# 10_USB.net
KiCad netlist of a schematic drawn in Altium Designer
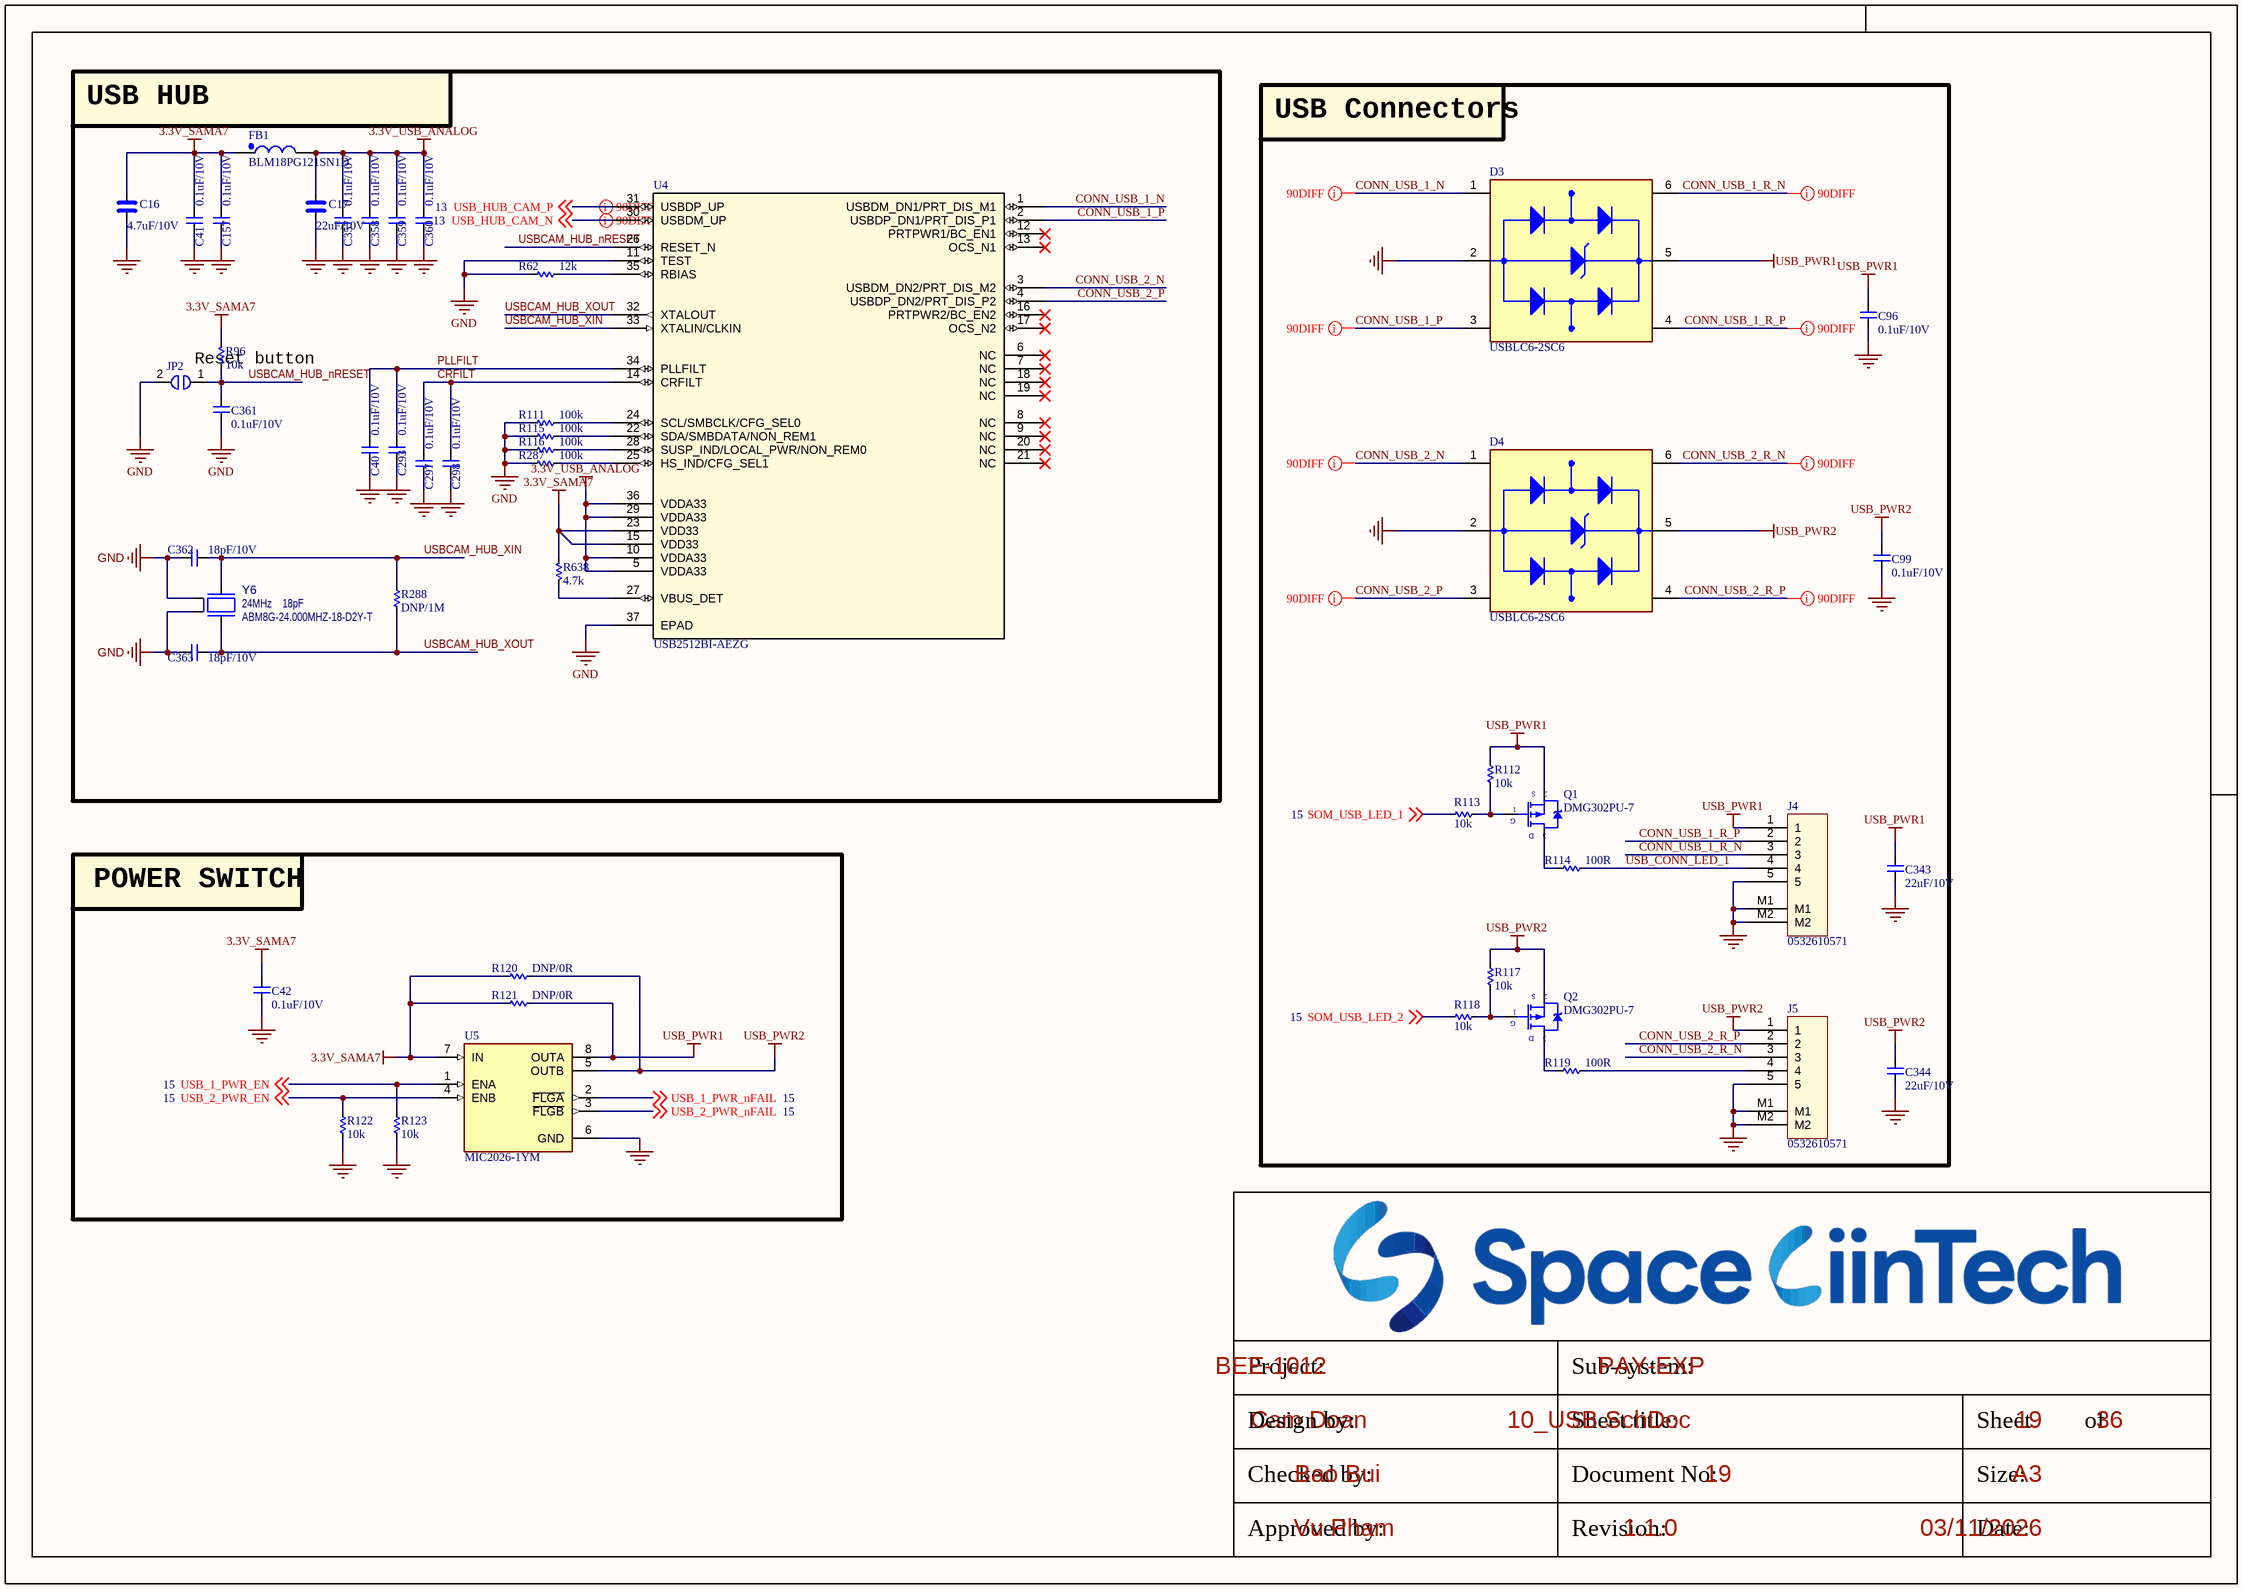
[diagram p0: 10_USB.SchDoc]

(export (version "E")
  (design (tool "Eeschema 10.0.6"))
  (components
    (comp (ref "C16")
      (value "4.7uF/10V")
      (footprint "CAP_C_1608X80")
      (description "CAP CHIP High Value")
      (libsource (lib "LABLIB") (part "_CAP_C_High_2"))
    )
    (comp (ref "C17")
      (value "22uF/10V")
      (footprint "CAP_C_1608X80")
      (description "CAP CHIP High Value")
      (libsource (lib "LABLIB") (part "_CAP_C_High_2"))
    )
    (comp (ref "C40")
      (value "0.1uF/10V")
      (footprint "CAP_C_1005X60")
      (description "CAP CHIP")
      (libsource (lib "LABLIB") (part "_CAP_C_2"))
    )
    (comp (ref "C41")
      (value "0.1uF/10V")
      (footprint "CAP_C_1005X60")
      (description "CAP CHIP")
      (libsource (lib "LABLIB") (part "_CAP_C_2"))
    )
    (comp (ref "C42")
      (value "0.1uF/10V")
      (footprint "CAP_C_1005X60")
      (description "CAP")
      (libsource (lib "LABLIB") (part "_CAP_C_2"))
    )
    (comp (ref "C96")
      (value "0.1uF/10V")
      (footprint "CAP_C_1005X60")
      (description "CAP")
      (libsource (lib "LABLIB") (part "_CAP_C_2"))
    )
    (comp (ref "C99")
      (value "0.1uF/10V")
      (footprint "CAP_C_1005X60")
      (description "CAP")
      (libsource (lib "LABLIB") (part "_CAP_C_2"))
    )
    (comp (ref "C157")
      (value "0.1uF/10V")
      (footprint "CAP_C_1005X60")
      (description "CAP CHIP")
      (libsource (lib "LABLIB") (part "_CAP_C_2"))
    )
    (comp (ref "C293")
      (value "0.1uF/10V")
      (footprint "CAP_C_1005X60")
      (description "CAP CHIP")
      (libsource (lib "LABLIB") (part "_CAP_C_2"))
    )
    (comp (ref "C297")
      (value "0.1uF/10V")
      (footprint "CAP_C_1005X60")
      (description "CAP CHIP")
      (libsource (lib "LABLIB") (part "_CAP_C_2"))
    )
    (comp (ref "C298")
      (value "0.1uF/10V")
      (footprint "CAP_C_1005X60")
      (description "CAP CHIP")
      (libsource (lib "LABLIB") (part "_CAP_C_2"))
    )
    (comp (ref "C343")
      (value "22uF/10V")
      (footprint "CAP_C_1608X80")
      (description "CAP")
      (libsource (lib "LABLIB") (part "_CAP_C_2"))
    )
    (comp (ref "C344")
      (value "22uF/10V")
      (footprint "CAP_C_1608X80")
      (description "CAP")
      (libsource (lib "LABLIB") (part "_CAP_C_2"))
    )
    (comp (ref "C357")
      (value "0.1uF/10V")
      (footprint "CAP_C_1005X60")
      (description "CAP CHIP")
      (libsource (lib "LABLIB") (part "_CAP_C_2"))
    )
    (comp (ref "C358")
      (value "0.1uF/10V")
      (footprint "CAP_C_1005X60")
      (description "CAP CHIP")
      (libsource (lib "LABLIB") (part "_CAP_C_2"))
    )
    (comp (ref "C359")
      (value "0.1uF/10V")
      (footprint "CAP_C_1005X60")
      (description "CAP CHIP")
      (libsource (lib "LABLIB") (part "_CAP_C_2"))
    )
    (comp (ref "C360")
      (value "0.1uF/10V")
      (footprint "CAP_C_1005X60")
      (description "CAP CHIP")
      (libsource (lib "LABLIB") (part "_CAP_C_2"))
    )
    (comp (ref "C361")
      (value "0.1uF/10V")
      (footprint "CAP_C_1005X60")
      (description "CAP CHIP")
      (libsource (lib "LABLIB") (part "_CAP_C_2"))
    )
    (comp (ref "C362")
      (value "18pF/10V")
      (footprint "CAP_C_1005X60")
      (description "CAP CHIP")
      (libsource (lib "LABLIB") (part "_CAP_C_2"))
    )
    (comp (ref "C363")
      (value "18pF/10V")
      (footprint "CAP_C_1005X60")
      (description "CAP CHIP")
      (libsource (lib "LABLIB") (part "_CAP_C_2"))
    )
    (comp (ref "D3")
      (value "USBLC6-2SC6")
      (footprint "SOT95P280X145-6N")
      (description "17V Clamp 5A (8/20Âµs) Ipp Tvs Diode Surface Mount SOT-23-6")
      (fields (field (name "MF") "STMicroelectronics"))
      (libsource (lib "USBLC6-2SC6") (part "USBLC6-2SC6"))
    )
    (comp (ref "D4")
      (value "USBLC6-2SC6")
      (footprint "SOT95P280X145-6N")
      (description "17V Clamp 5A (8/20Âµs) Ipp Tvs Diode Surface Mount SOT-23-6")
      (fields (field (name "MF") "STMicroelectronics"))
      (libsource (lib "USBLC6-2SC6") (part "USBLC6-2SC6"))
    )
    (comp (ref "FB1")
      (value "BLM18PG121SN1D")
      (footprint "IND_C_1608X60")
      (libsource (lib "LABLIB") (part "_IND"))
    )
    (comp (ref "J4")
      (value "0532610571")
      (footprint "MOLEX_0532610571")
      (libsource (lib "LABLIB") (part "Header 5x1_2M"))
    )
    (comp (ref "J5")
      (value "0532610571")
      (footprint "MOLEX_0532610571")
      (libsource (lib "LABLIB") (part "Header 5x1_2M"))
    )
    (comp (ref "JP2")
      (value "~")
      (footprint "TESTPOINT_SHORT_120X100_60")
      (libsource (lib "LABLIB") (part "JUMPER_1_1"))
    )
    (comp (ref "Q1")
      (value "DMG302PU-7")
      (footprint "SOT95P240X120-3N")
      (libsource (lib "LABLIB") (part "MOSFET_P_GSD"))
    )
    (comp (ref "Q2")
      (value "DMG302PU-7")
      (footprint "SOT95P240X120-3N")
      (libsource (lib "LABLIB") (part "MOSFET_P_GSD"))
    )
    (comp (ref "R62")
      (value "12k")
      (footprint "RES_C_1005X40")
      (description "RES")
      (libsource (lib "LABLIB") (part "_RES_B_2"))
    )
    (comp (ref "R96")
      (value "10k")
      (footprint "RES_C_1005X40")
      (description "RES")
      (libsource (lib "LABLIB") (part "_RES_B_2"))
    )
    (comp (ref "R111")
      (value "100k")
      (footprint "RES_C_1005X40")
      (description "RES")
      (libsource (lib "LABLIB") (part "_RES_B_2"))
    )
    (comp (ref "R112")
      (value "10k")
      (footprint "RES_C_1005X40")
      (description "RES")
      (libsource (lib "LABLIB") (part "_RES_B_2"))
    )
    (comp (ref "R113")
      (value "10k")
      (footprint "RES_C_1005X40")
      (description "RES")
      (libsource (lib "LABLIB") (part "_RES_B_2"))
    )
    (comp (ref "R114")
      (value "100R")
      (footprint "RES_C_1005X40")
      (description "RES")
      (libsource (lib "LABLIB") (part "_RES_B_2"))
    )
    (comp (ref "R115")
      (value "100k")
      (footprint "RES_C_1005X40")
      (description "RES")
      (libsource (lib "LABLIB") (part "_RES_B_2"))
    )
    (comp (ref "R116")
      (value "100k")
      (footprint "RES_C_1005X40")
      (description "RES")
      (libsource (lib "LABLIB") (part "_RES_B_2"))
    )
    (comp (ref "R117")
      (value "10k")
      (footprint "RES_C_1005X40")
      (description "RES")
      (libsource (lib "LABLIB") (part "_RES_B_2"))
    )
    (comp (ref "R118")
      (value "10k")
      (footprint "RES_C_1005X40")
      (description "RES")
      (libsource (lib "LABLIB") (part "_RES_B_2"))
    )
    (comp (ref "R119")
      (value "100R")
      (footprint "RES_C_1005X40")
      (description "RES")
      (libsource (lib "LABLIB") (part "_RES_B_2"))
    )
    (comp (ref "R120")
      (value "DNP/0R")
      (footprint "RES_C_1005X40")
      (description "RES")
      (libsource (lib "LABLIB") (part "_RES_B_2"))
    )
    (comp (ref "R121")
      (value "DNP/0R")
      (footprint "RES_C_1005X40")
      (description "RES")
      (libsource (lib "LABLIB") (part "_RES_B_2"))
    )
    (comp (ref "R122")
      (value "10k")
      (footprint "RES_C_1005X40")
      (description "RES")
      (libsource (lib "LABLIB") (part "_RES_B_2"))
    )
    (comp (ref "R123")
      (value "10k")
      (footprint "RES_C_1005X40")
      (description "RES")
      (libsource (lib "LABLIB") (part "_RES_B_2"))
    )
    (comp (ref "R287")
      (value "100k")
      (footprint "RES_C_1005X40")
      (description "RES")
      (libsource (lib "LABLIB") (part "_RES_B_2"))
    )
    (comp (ref "R288")
      (value "DNP/1M")
      (footprint "RES_C_1005X40")
      (description "RES")
      (libsource (lib "LABLIB") (part "_RES_B_2"))
    )
    (comp (ref "R638")
      (value "4.7k")
      (footprint "RES_C_1005X40")
      (description "RES")
      (libsource (lib "LABLIB") (part "_RES_B_2"))
    )
    (comp (ref "U4")
      (value "USB2512BI-AEZG")
      (footprint "QFN36_6X6MC_MCH")
      (description "Description")
      (fields (field (name "COPYRIGHT") "Copyright (C) 2026 Ultra Librarian. All rights reserved."))
      (libsource (lib "LABLIB") (part "IC_USB_HUB_USB2512BI-AEZG"))
    )
    (comp (ref "U5")
      (value "MIC2026-1YM")
      (footprint "SOIC127P602X173-8N")
      (description "Power Switch/Driver 1:2 N-Channel 1.25A 8-SOIC")
      (fields (field (name "MF") "Microchip"))
      (libsource (lib "LABLIB") (part "IC_PWRSW_MIC2026-1YM"))
    )
    (comp (ref "Y6")
      (value "24MHz")
      (footprint "CRYSTAL_ABM8G")
      (description "Crystal")
      (fields
        (field (name "LOAD CAPACITANCE") "18pF")
        (field (name "MANUFACTURER PART NUMBER 1") "ABM8G-24.000MHZ-18-D2Y-T")
        (field (name "Comment") "Crystal 4 Pins")
        (field (name "OWNER") "Mark Loper")
      )
      (libsource (lib "MCHP-CDB") (part "Crystal 4 Pins"))
    )
  )
  (nets
    (net (code "1") (name "/CONN_USB_1_N") (class "Default")
      (node (ref "D3") (pin "1") (pinfunction "I/O1_IN_1") (pintype "passive"))
      (node (ref "U4") (pin "1") (pinfunction "USBDM_DN1/PRT_DIS_M1_1") (pintype "bidirectional"))
    )
    (net (code "2") (name "/CONN_USB_1_P") (class "Default")
      (node (ref "D3") (pin "3") (pinfunction "I/O2_IN_3") (pintype "passive"))
      (node (ref "U4") (pin "2") (pinfunction "USBDP_DN1/PRT_DIS_P1_2") (pintype "bidirectional"))
    )
    (net (code "3") (name "/CONN_USB_1_R_N") (class "Default")
      (node (ref "D3") (pin "6") (pinfunction "I/O1_OUT_6") (pintype "passive"))
      (node (ref "J4") (pin "3") (pinfunction "3_3") (pintype "passive"))
    )
    (net (code "4") (name "/CONN_USB_1_R_P") (class "Default")
      (node (ref "D3") (pin "4") (pinfunction "I/O2_OUT_4") (pintype "passive"))
      (node (ref "J4") (pin "2") (pinfunction "2_2") (pintype "passive"))
    )
    (net (code "5") (name "/CONN_USB_2_N") (class "Default")
      (node (ref "D4") (pin "1") (pinfunction "I/O1_IN_1") (pintype "passive"))
      (node (ref "U4") (pin "3") (pinfunction "USBDM_DN2/PRT_DIS_M2_3") (pintype "bidirectional"))
    )
    (net (code "6") (name "/CONN_USB_2_P") (class "Default")
      (node (ref "D4") (pin "3") (pinfunction "I/O2_IN_3") (pintype "passive"))
      (node (ref "U4") (pin "4") (pinfunction "USBDP_DN2/PRT_DIS_P2_4") (pintype "bidirectional"))
    )
    (net (code "7") (name "/CONN_USB_2_R_N") (class "Default")
      (node (ref "D4") (pin "6") (pinfunction "I/O1_OUT_6") (pintype "passive"))
      (node (ref "J5") (pin "3") (pinfunction "3_3") (pintype "passive"))
    )
    (net (code "8") (name "/CONN_USB_2_R_P") (class "Default")
      (node (ref "D4") (pin "4") (pinfunction "I/O2_OUT_4") (pintype "passive"))
      (node (ref "J5") (pin "2") (pinfunction "2_2") (pintype "passive"))
    )
    (net (code "9") (name "/CRFILT") (class "Default")
      (node (ref "C297") (pin "2") (pinfunction "2_2") (pintype "passive"))
      (node (ref "C298") (pin "2") (pinfunction "2_2") (pintype "passive"))
      (node (ref "U4") (pin "14") (pinfunction "CRFILT_14") (pintype "bidirectional"))
    )
    (net (code "10") (name "/PLLFILT") (class "Default")
      (node (ref "C293") (pin "2") (pinfunction "2_2") (pintype "passive"))
      (node (ref "C40") (pin "2") (pinfunction "2_2") (pintype "passive"))
      (node (ref "U4") (pin "34") (pinfunction "PLLFILT_34") (pintype "bidirectional"))
    )
    (net (code "11") (name "/USBCAM_HUB_XIN") (class "Default")
      (node (ref "C362") (pin "1") (pinfunction "1_1") (pintype "passive"))
      (node (ref "R288") (pin "1") (pinfunction "1_1") (pintype "passive"))
      (node (ref "U4") (pin "33") (pinfunction "XTALIN/CLKIN_33") (pintype "input"))
      (node (ref "Y6") (pin "3") (pinfunction "Osc2_3") (pintype "passive"))
    )
    (net (code "12") (name "/USBCAM_HUB_XOUT") (class "Default")
      (node (ref "C363") (pin "1") (pinfunction "1_1") (pintype "passive"))
      (node (ref "R288") (pin "2") (pinfunction "2_2") (pintype "passive"))
      (node (ref "U4") (pin "32") (pinfunction "XTALOUT_32") (pintype "output"))
      (node (ref "Y6") (pin "1") (pinfunction "Osc1_1") (pintype "passive"))
    )
    (net (code "13") (name "/USBCAM_HUB_nRESET") (class "Default")
      (node (ref "C361") (pin "2") (pinfunction "2_2") (pintype "passive"))
      (node (ref "JP2") (pin "1") (pinfunction "1_1") (pintype "passive"))
      (node (ref "R96") (pin "2") (pinfunction "2_2") (pintype "passive"))
      (node (ref "U4") (pin "26") (pinfunction "RESET_N_26") (pintype "bidirectional"))
    )
    (net (code "14") (name "/USB_CONN_LED_1") (class "Default")
      (node (ref "J4") (pin "4") (pinfunction "4_4") (pintype "passive"))
      (node (ref "R114") (pin "2") (pinfunction "2_2") (pintype "passive"))
    )
    (net (code "15") (name "3.3V_SAMA7") (class "Default")
      (node (ref "C157") (pin "2") (pinfunction "2_2") (pintype "passive"))
      (node (ref "C16") (pin "1") (pinfunction "1_1") (pintype "passive"))
      (node (ref "C41") (pin "2") (pinfunction "2_2") (pintype "passive"))
      (node (ref "C42") (pin "2") (pinfunction "2_2") (pintype "passive"))
      (node (ref "FB1") (pin "1") (pinfunction "1_1") (pintype "passive"))
      (node (ref "R120") (pin "2") (pinfunction "2_2") (pintype "passive"))
      (node (ref "R121") (pin "2") (pinfunction "2_2") (pintype "passive"))
      (node (ref "R638") (pin "1") (pinfunction "1_1") (pintype "passive"))
      (node (ref "R96") (pin "1") (pinfunction "1_1") (pintype "passive"))
      (node (ref "U4") (pin "15") (pinfunction "VDD33_15") (pintype "power_in"))
      (node (ref "U4") (pin "23") (pinfunction "VDD33_23") (pintype "power_in"))
      (node (ref "U5") (pin "7") (pinfunction "IN_7") (pintype "input"))
    )
    (net (code "16") (name "3.3V_USB_ANALOG") (class "Default")
      (node (ref "C17") (pin "1") (pinfunction "1_1") (pintype "passive"))
      (node (ref "C357") (pin "2") (pinfunction "2_2") (pintype "passive"))
      (node (ref "C358") (pin "2") (pinfunction "2_2") (pintype "passive"))
      (node (ref "C359") (pin "2") (pinfunction "2_2") (pintype "passive"))
      (node (ref "C360") (pin "2") (pinfunction "2_2") (pintype "passive"))
      (node (ref "FB1") (pin "2") (pinfunction "2_2") (pintype "passive"))
      (node (ref "U4") (pin "10") (pinfunction "VDDA33_10") (pintype "power_in"))
      (node (ref "U4") (pin "29") (pinfunction "VDDA33_29") (pintype "power_in"))
      (node (ref "U4") (pin "36") (pinfunction "VDDA33_36") (pintype "power_in"))
      (node (ref "U4") (pin "5") (pinfunction "VDDA33_5") (pintype "power_in"))
    )
    (net (code "17") (name "GND") (class "Default")
      (node (ref "C157") (pin "1") (pinfunction "1_1") (pintype "passive"))
      (node (ref "C16") (pin "2") (pinfunction "2_2") (pintype "passive"))
      (node (ref "C17") (pin "2") (pinfunction "2_2") (pintype "passive"))
      (node (ref "C293") (pin "1") (pinfunction "1_1") (pintype "passive"))
      (node (ref "C297") (pin "1") (pinfunction "1_1") (pintype "passive"))
      (node (ref "C298") (pin "1") (pinfunction "1_1") (pintype "passive"))
      (node (ref "C343") (pin "1") (pinfunction "1_1") (pintype "passive"))
      (node (ref "C344") (pin "1") (pinfunction "1_1") (pintype "passive"))
      (node (ref "C357") (pin "1") (pinfunction "1_1") (pintype "passive"))
      (node (ref "C358") (pin "1") (pinfunction "1_1") (pintype "passive"))
      (node (ref "C359") (pin "1") (pinfunction "1_1") (pintype "passive"))
      (node (ref "C360") (pin "1") (pinfunction "1_1") (pintype "passive"))
      (node (ref "C361") (pin "1") (pinfunction "1_1") (pintype "passive"))
      (node (ref "C362") (pin "2") (pinfunction "2_2") (pintype "passive"))
      (node (ref "C363") (pin "2") (pinfunction "2_2") (pintype "passive"))
      (node (ref "C40") (pin "1") (pinfunction "1_1") (pintype "passive"))
      (node (ref "C41") (pin "1") (pinfunction "1_1") (pintype "passive"))
      (node (ref "C42") (pin "1") (pinfunction "1_1") (pintype "passive"))
      (node (ref "C96") (pin "1") (pinfunction "1_1") (pintype "passive"))
      (node (ref "C99") (pin "1") (pinfunction "1_1") (pintype "passive"))
      (node (ref "D3") (pin "2") (pinfunction "GND_2") (pintype "power_in"))
      (node (ref "D4") (pin "2") (pinfunction "GND_2") (pintype "power_in"))
      (node (ref "J4") (pin "5") (pinfunction "5_5") (pintype "passive"))
      (node (ref "J4") (pin "M1") (pinfunction "M1_M1") (pintype "passive"))
      (node (ref "J4") (pin "M2") (pinfunction "M2_M2") (pintype "passive"))
      (node (ref "J5") (pin "5") (pinfunction "5_5") (pintype "passive"))
      (node (ref "J5") (pin "M1") (pinfunction "M1_M1") (pintype "passive"))
      (node (ref "J5") (pin "M2") (pinfunction "M2_M2") (pintype "passive"))
      (node (ref "JP2") (pin "2") (pinfunction "2_2") (pintype "passive"))
      (node (ref "R111") (pin "1") (pinfunction "1_1") (pintype "passive"))
      (node (ref "R115") (pin "1") (pinfunction "1_1") (pintype "passive"))
      (node (ref "R116") (pin "1") (pinfunction "1_1") (pintype "passive"))
      (node (ref "R122") (pin "2") (pinfunction "2_2") (pintype "passive"))
      (node (ref "R123") (pin "2") (pinfunction "2_2") (pintype "passive"))
      (node (ref "R287") (pin "1") (pinfunction "1_1") (pintype "passive"))
      (node (ref "R62") (pin "1") (pinfunction "1_1") (pintype "passive"))
      (node (ref "U4") (pin "11") (pinfunction "TEST_11") (pintype "bidirectional"))
      (node (ref "U4") (pin "37") (pinfunction "EPAD_37") (pintype "passive"))
      (node (ref "U5") (pin "6") (pinfunction "GND_6") (pintype "power_in"))
      (node (ref "Y6") (pin "2") (pinfunction "GND_2") (pintype "power_in"))
      (node (ref "Y6") (pin "4") (pinfunction "GND_4") (pintype "power_in"))
    )
    (net (code "18") (name "Net-(J5-Pad4)") (class "Default")
      (node (ref "J5") (pin "4") (pinfunction "4_4") (pintype "passive"))
      (node (ref "R119") (pin "2") (pinfunction "2_2") (pintype "passive"))
    )
    (net (code "19") (name "Net-(Q1-D)") (class "Default")
      (node (ref "Q1") (pin "3") (pinfunction "D_3") (pintype "passive"))
      (node (ref "R114") (pin "1") (pinfunction "1_1") (pintype "passive"))
    )
    (net (code "20") (name "Net-(Q1-G)") (class "Default")
      (node (ref "Q1") (pin "1") (pinfunction "G_1") (pintype "passive"))
      (node (ref "R112") (pin "2") (pinfunction "2_2") (pintype "passive"))
      (node (ref "R113") (pin "2") (pinfunction "2_2") (pintype "passive"))
    )
    (net (code "21") (name "Net-(Q2-D)") (class "Default")
      (node (ref "Q2") (pin "3") (pinfunction "D_3") (pintype "passive"))
      (node (ref "R119") (pin "1") (pinfunction "1_1") (pintype "passive"))
    )
    (net (code "22") (name "Net-(Q2-G)") (class "Default")
      (node (ref "Q2") (pin "1") (pinfunction "G_1") (pintype "passive"))
      (node (ref "R117") (pin "2") (pinfunction "2_2") (pintype "passive"))
      (node (ref "R118") (pin "2") (pinfunction "2_2") (pintype "passive"))
    )
    (net (code "23") (name "Net-(U4-HS_IND{slash}CFG_SEL1)") (class "Default")
      (node (ref "R287") (pin "2") (pinfunction "2_2") (pintype "passive"))
      (node (ref "U4") (pin "25") (pinfunction "HS_IND/CFG_SEL1_25") (pintype "bidirectional"))
    )
    (net (code "24") (name "Net-(U4-RBIAS)") (class "Default")
      (node (ref "R62") (pin "2") (pinfunction "2_2") (pintype "passive"))
      (node (ref "U4") (pin "35") (pinfunction "RBIAS_35") (pintype "bidirectional"))
    )
    (net (code "25") (name "Net-(U4-SCL{slash}SMBCLK{slash}CFG_SEL0)") (class "Default")
      (node (ref "R111") (pin "2") (pinfunction "2_2") (pintype "passive"))
      (node (ref "U4") (pin "24") (pinfunction "SCL/SMBCLK/CFG_SEL0_24") (pintype "bidirectional"))
    )
    (net (code "26") (name "Net-(U4-SDA{slash}SMBDATA{slash}NON_REM1)") (class "Default")
      (node (ref "R115") (pin "2") (pinfunction "2_2") (pintype "passive"))
      (node (ref "U4") (pin "22") (pinfunction "SDA/SMBDATA/NON_REM1_22") (pintype "bidirectional"))
    )
    (net (code "27") (name "Net-(U4-SUSP_IND{slash}LOCAL_PWR{slash}NON_REM0)") (class "Default")
      (node (ref "R116") (pin "2") (pinfunction "2_2") (pintype "passive"))
      (node (ref "U4") (pin "28") (pinfunction "SUSP_IND/LOCAL_PWR/NON_REM0_28") (pintype "bidirectional"))
    )
    (net (code "28") (name "Net-(U4-VBUS_DET)") (class "Default")
      (node (ref "R638") (pin "2") (pinfunction "2_2") (pintype "passive"))
      (node (ref "U4") (pin "27") (pinfunction "VBUS_DET_27") (pintype "bidirectional"))
    )
    (net (code "29") (name "SOM_USB_LED_1") (class "Default")
      (node (ref "R113") (pin "1") (pinfunction "1_1") (pintype "passive"))
    )
    (net (code "30") (name "SOM_USB_LED_2") (class "Default")
      (node (ref "R118") (pin "1") (pinfunction "1_1") (pintype "passive"))
    )
    (net (code "31") (name "USB_1_PWR_EN") (class "Default")
      (node (ref "R123") (pin "1") (pinfunction "1_1") (pintype "passive"))
      (node (ref "U5") (pin "1") (pinfunction "ENA_1") (pintype "input"))
    )
    (net (code "32") (name "USB_1_PWR_nFAIL") (class "Default")
      (node (ref "U5") (pin "2") (pinfunction "~{FLGA}_2") (pintype "output"))
    )
    (net (code "33") (name "USB_2_PWR_EN") (class "Default")
      (node (ref "R122") (pin "1") (pinfunction "1_1") (pintype "passive"))
      (node (ref "U5") (pin "4") (pinfunction "ENB_4") (pintype "input"))
    )
    (net (code "34") (name "USB_2_PWR_nFAIL") (class "Default")
      (node (ref "U5") (pin "3") (pinfunction "~{FLGB}_3") (pintype "output"))
    )
    (net (code "35") (name "USB_HUB_CAM_N") (class "Default")
      (node (ref "U4") (pin "30") (pinfunction "USBDM_UP_30") (pintype "bidirectional"))
    )
    (net (code "36") (name "USB_HUB_CAM_P") (class "Default")
      (node (ref "U4") (pin "31") (pinfunction "USBDP_UP_31") (pintype "bidirectional"))
    )
    (net (code "37") (name "USB_PWR1") (class "Default")
      (node (ref "C343") (pin "2") (pinfunction "2_2") (pintype "passive"))
      (node (ref "C96") (pin "2") (pinfunction "2_2") (pintype "passive"))
      (node (ref "D3") (pin "5") (pinfunction "VBUS_5") (pintype "power_in"))
      (node (ref "J4") (pin "1") (pinfunction "1_1") (pintype "passive"))
      (node (ref "Q1") (pin "2") (pinfunction "S_2") (pintype "passive"))
      (node (ref "R112") (pin "1") (pinfunction "1_1") (pintype "passive"))
      (node (ref "R121") (pin "1") (pinfunction "1_1") (pintype "passive"))
      (node (ref "U5") (pin "8") (pinfunction "OUTA_8") (pintype "passive"))
    )
    (net (code "38") (name "USB_PWR2") (class "Default")
      (node (ref "C344") (pin "2") (pinfunction "2_2") (pintype "passive"))
      (node (ref "C99") (pin "2") (pinfunction "2_2") (pintype "passive"))
      (node (ref "D4") (pin "5") (pinfunction "VBUS_5") (pintype "power_in"))
      (node (ref "J5") (pin "1") (pinfunction "1_1") (pintype "passive"))
      (node (ref "Q2") (pin "2") (pinfunction "S_2") (pintype "passive"))
      (node (ref "R117") (pin "1") (pinfunction "1_1") (pintype "passive"))
      (node (ref "R120") (pin "1") (pinfunction "1_1") (pintype "passive"))
      (node (ref "U5") (pin "5") (pinfunction "OUTB_5") (pintype "passive"))
    )
    (net (code "39") (name "unconnected-(U4-NC-Pad6)") (class "Default")
      (node (ref "U4") (pin "6") (pinfunction "NC_6") (pintype "passive+no_connect"))
    )
    (net (code "40") (name "unconnected-(U4-NC-Pad7)") (class "Default")
      (node (ref "U4") (pin "7") (pinfunction "NC_7") (pintype "passive+no_connect"))
    )
    (net (code "41") (name "unconnected-(U4-NC-Pad8)") (class "Default")
      (node (ref "U4") (pin "8") (pinfunction "NC_8") (pintype "passive+no_connect"))
    )
    (net (code "42") (name "unconnected-(U4-NC-Pad9)") (class "Default")
      (node (ref "U4") (pin "9") (pinfunction "NC_9") (pintype "passive+no_connect"))
    )
    (net (code "43") (name "unconnected-(U4-NC-Pad18)") (class "Default")
      (node (ref "U4") (pin "18") (pinfunction "NC_18") (pintype "passive+no_connect"))
    )
    (net (code "44") (name "unconnected-(U4-NC-Pad19)") (class "Default")
      (node (ref "U4") (pin "19") (pinfunction "NC_19") (pintype "passive+no_connect"))
    )
    (net (code "45") (name "unconnected-(U4-NC-Pad20)") (class "Default")
      (node (ref "U4") (pin "20") (pinfunction "NC_20") (pintype "passive+no_connect"))
    )
    (net (code "46") (name "unconnected-(U4-NC-Pad21)") (class "Default")
      (node (ref "U4") (pin "21") (pinfunction "NC_21") (pintype "passive+no_connect"))
    )
    (net (code "47") (name "unconnected-(U4-OCS_N1-Pad13)") (class "Default")
      (node (ref "U4") (pin "13") (pinfunction "OCS_N1_13") (pintype "bidirectional+no_connect"))
    )
    (net (code "48") (name "unconnected-(U4-OCS_N2-Pad17)") (class "Default")
      (node (ref "U4") (pin "17") (pinfunction "OCS_N2_17") (pintype "bidirectional+no_connect"))
    )
    (net (code "49") (name "unconnected-(U4-PRTPWR1{slash}BC_EN1-Pad12)") (class "Default")
      (node (ref "U4") (pin "12") (pinfunction "PRTPWR1/BC_EN1_12") (pintype "bidirectional+no_connect"))
    )
    (net (code "50") (name "unconnected-(U4-PRTPWR2{slash}BC_EN2-Pad16)") (class "Default")
      (node (ref "U4") (pin "16") (pinfunction "PRTPWR2/BC_EN2_16") (pintype "bidirectional+no_connect"))
    )
  )
)
